# supply.net
KiCad netlist of a schematic drawn in EAGLE
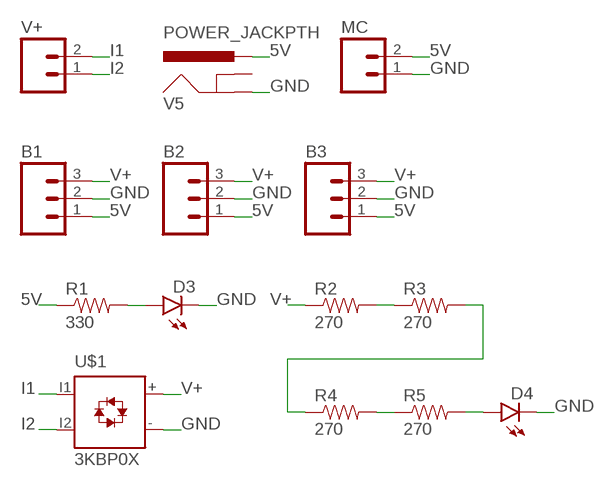
[diagram p0: schematic, sheet 1]

(export (version "E")
  (design (tool "Eeschema 10.0.6"))
  (components
    (comp (ref "B1")
      (value "M03PTH")
      (footprint "eagle-import:1X03")
      (libsource (lib "eagle-import") (part "M03PTH"))
    )
    (comp (ref "B2")
      (value "M03PTH")
      (footprint "eagle-import:1X03")
      (libsource (lib "eagle-import") (part "M03PTH"))
    )
    (comp (ref "B3")
      (value "M03PTH")
      (footprint "eagle-import:1X03")
      (libsource (lib "eagle-import") (part "M03PTH"))
    )
    (comp (ref "D3")
      (value "LED10MM")
      (footprint "eagle-import:LED10MM")
      (libsource (lib "eagle-import") (part "LED10MM"))
    )
    (comp (ref "D4")
      (value "LED10MM")
      (footprint "eagle-import:LED10MM")
      (libsource (lib "eagle-import") (part "LED10MM"))
    )
    (comp (ref "MC")
      (value "M02PTH")
      (footprint "eagle-import:1X02")
      (libsource (lib "eagle-import") (part "M02PTH"))
    )
    (comp (ref "R1")
      (value "330")
      (footprint "eagle-import:AXIAL-0.3EZ")
      (libsource (lib "eagle-import") (part "1KOHM-1/4W-5%(PTH)HORIZ-KIT"))
    )
    (comp (ref "R2")
      (value "270")
      (footprint "eagle-import:AXIAL-0.3EZ")
      (libsource (lib "eagle-import") (part "1KOHM-1/4W-5%(PTH)HORIZ-KIT"))
    )
    (comp (ref "R3")
      (value "270")
      (footprint "eagle-import:AXIAL-0.3EZ")
      (libsource (lib "eagle-import") (part "1KOHM-1/4W-5%(PTH)HORIZ-KIT"))
    )
    (comp (ref "R4")
      (value "270")
      (footprint "eagle-import:AXIAL-0.3EZ")
      (libsource (lib "eagle-import") (part "1KOHM-1/4W-5%(PTH)HORIZ-KIT"))
    )
    (comp (ref "R5")
      (value "270")
      (footprint "eagle-import:AXIAL-0.3EZ")
      (libsource (lib "eagle-import") (part "1KOHM-1/4W-5%(PTH)HORIZ-KIT"))
    )
    (comp (ref "U$1")
      (value "3KBP0X")
      (footprint "eagle-import:3KBP0X")
      (libsource (lib "eagle-import") (part "3KBP0X"))
    )
    (comp (ref "V+")
      (value "M025MM")
      (footprint "eagle-import:SCREWTERMINAL-5MM-2")
      (libsource (lib "eagle-import") (part "M025MM"))
    )
    (comp (ref "V5")
      (value "POWER_JACKPTH")
      (footprint "eagle-import:POWER_JACK_PTH")
      (libsource (lib "eagle-import") (part "POWER_JACKPTH"))
    )
  )
  (nets
    (net (code "1") (name "/5V") (class "Default")
      (node (ref "B1") (pin "1") (pinfunction "1_1") (pintype "passive"))
      (node (ref "B2") (pin "1") (pinfunction "1_1") (pintype "passive"))
      (node (ref "B3") (pin "1") (pinfunction "1_1") (pintype "passive"))
      (node (ref "MC") (pin "2") (pinfunction "2_2") (pintype "passive"))
      (node (ref "R1") (pin "P$1") (pinfunction "1_P$1") (pintype "passive"))
      (node (ref "V5") (pin "PWR") (pinfunction "PWR_PWR") (pintype "bidirectional"))
    )
    (net (code "2") (name "/GND") (class "Default")
      (node (ref "B1") (pin "2") (pinfunction "2_2") (pintype "passive"))
      (node (ref "B2") (pin "2") (pinfunction "2_2") (pintype "passive"))
      (node (ref "B3") (pin "2") (pinfunction "2_2") (pintype "passive"))
      (node (ref "D3") (pin "C") (pinfunction "C_C") (pintype "passive"))
      (node (ref "D4") (pin "C") (pinfunction "C_C") (pintype "passive"))
      (node (ref "MC") (pin "1") (pinfunction "1_1") (pintype "passive"))
      (node (ref "U$1") (pin "-") (pinfunction "-_-") (pintype "bidirectional"))
      (node (ref "V5") (pin "GND") (pinfunction "GND_GND") (pintype "bidirectional"))
    )
    (net (code "3") (name "/I1") (class "Default")
      (node (ref "U$1") (pin "I1") (pinfunction "I1_I1") (pintype "bidirectional"))
      (node (ref "V+") (pin "2") (pinfunction "2_2") (pintype "passive"))
    )
    (net (code "4") (name "/I2") (class "Default")
      (node (ref "U$1") (pin "I2") (pinfunction "I2_I2") (pintype "bidirectional"))
      (node (ref "V+") (pin "1") (pinfunction "1_1") (pintype "passive"))
    )
    (net (code "5") (name "/V+") (class "Default")
      (node (ref "B1") (pin "3") (pinfunction "3_3") (pintype "passive"))
      (node (ref "B2") (pin "3") (pinfunction "3_3") (pintype "passive"))
      (node (ref "B3") (pin "3") (pinfunction "3_3") (pintype "passive"))
      (node (ref "R2") (pin "P$1") (pinfunction "1_P$1") (pintype "passive"))
      (node (ref "U$1") (pin "+") (pinfunction "+_+") (pintype "bidirectional"))
    )
    (net (code "6") (name "Net-(R1-2)") (class "Default")
      (node (ref "D3") (pin "A") (pinfunction "A_A") (pintype "passive"))
      (node (ref "R1") (pin "P$2") (pinfunction "2_P$2") (pintype "passive"))
    )
    (net (code "7") (name "Net-(R2-2)") (class "Default")
      (node (ref "R2") (pin "P$2") (pinfunction "2_P$2") (pintype "passive"))
      (node (ref "R3") (pin "P$1") (pinfunction "1_P$1") (pintype "passive"))
    )
    (net (code "8") (name "Net-(R3-2)") (class "Default")
      (node (ref "R3") (pin "P$2") (pinfunction "2_P$2") (pintype "passive"))
      (node (ref "R4") (pin "P$1") (pinfunction "1_P$1") (pintype "passive"))
    )
    (net (code "9") (name "Net-(R4-2)") (class "Default")
      (node (ref "R4") (pin "P$2") (pinfunction "2_P$2") (pintype "passive"))
      (node (ref "R5") (pin "P$1") (pinfunction "1_P$1") (pintype "passive"))
    )
    (net (code "10") (name "Net-(R5-2)") (class "Default")
      (node (ref "D4") (pin "A") (pinfunction "A_A") (pintype "passive"))
      (node (ref "R5") (pin "P$2") (pinfunction "2_P$2") (pintype "passive"))
    )
    (net (code "11") (name "unconnected-(V5-PadGNDBREAK)") (class "Default")
      (node (ref "V5") (pin "GNDBREAK") (pinfunction "GNDBREAK_GNDBREAK") (pintype "bidirectional"))
    )
  )
)
